# ARP_Odyssey_Ring_Mod_1_1.net
KiCad netlist of a schematic drawn in EAGLE
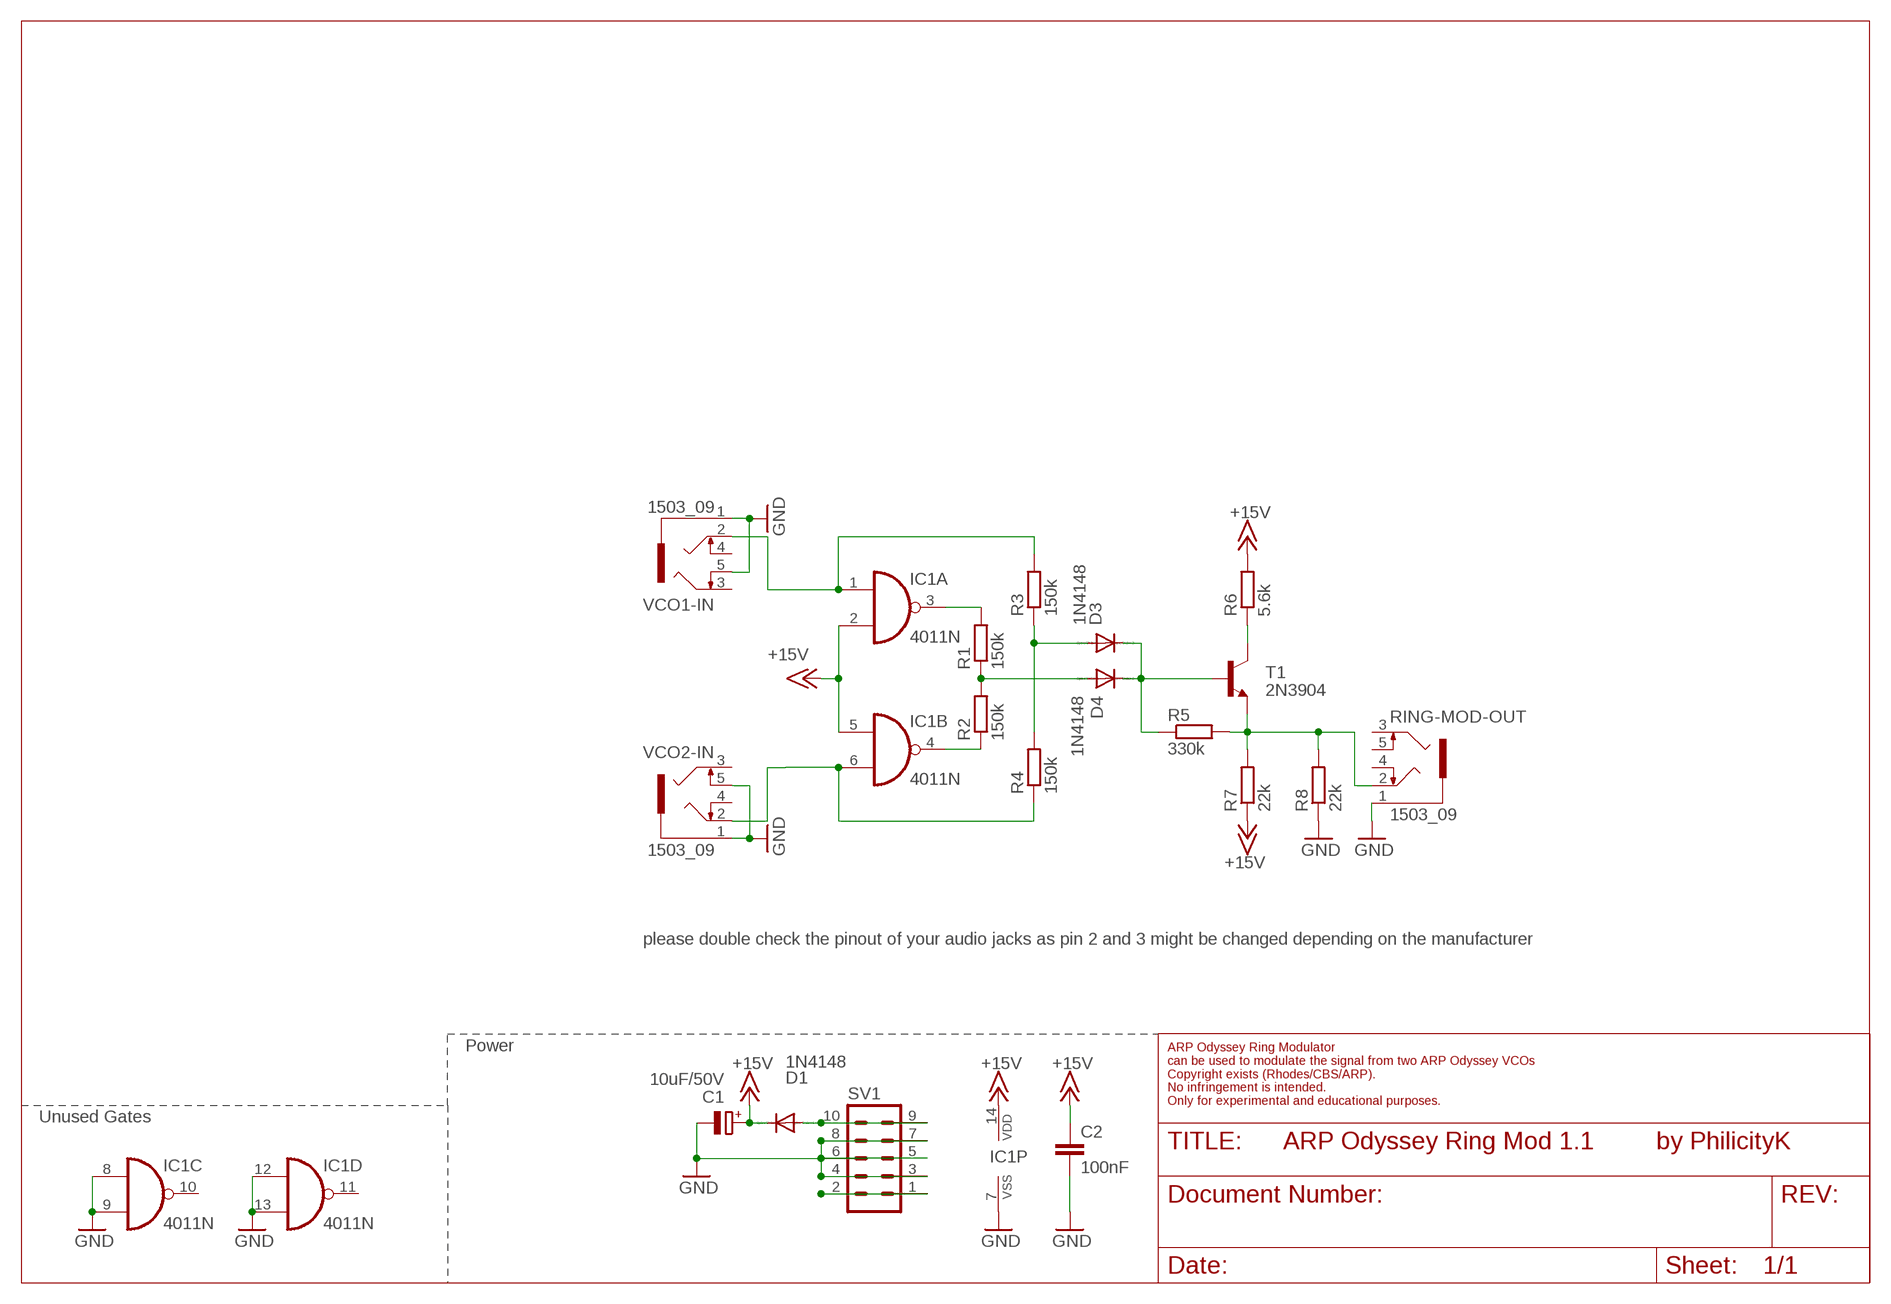
[diagram p0: schematic, sheet 1]

(export (version "E")
  (design (tool "Eeschema 10.0.6"))
  (components
    (comp (ref "C1")
      (value "10uF/50V")
      (footprint "eagle-import:E3,5-8")
      (libsource (lib "eagle-import") (part "CPOL-EUE3.5-8"))
    )
    (comp (ref "C2")
      (value "100nF")
      (footprint "eagle-import:C050-024X044")
      (libsource (lib "eagle-import") (part "C-EU050-024X044"))
    )
    (comp (ref "D1")
      (value "1N4148")
      (footprint "eagle-import:DO35-7")
      (libsource (lib "eagle-import") (part "1N4148DO35-7"))
    )
    (comp (ref "D3")
      (value "1N4148")
      (footprint "eagle-import:DO35-7")
      (libsource (lib "eagle-import") (part "1N4148DO35-7"))
    )
    (comp (ref "D4")
      (value "1N4148")
      (footprint "eagle-import:DO35-7")
      (libsource (lib "eagle-import") (part "1N4148DO35-7"))
    )
    (comp (ref "IC1")
      (value "4011N")
      (footprint "eagle-import:DIL14")
      (libsource (lib "eagle-import") (part "4011N"))
    )
    (comp (ref "R1")
      (value "150k")
      (footprint "eagle-import:0207_7")
      (libsource (lib "eagle-import") (part "R-EU_0207/7"))
    )
    (comp (ref "R2")
      (value "150k")
      (footprint "eagle-import:0207_7")
      (libsource (lib "eagle-import") (part "R-EU_0207/7"))
    )
    (comp (ref "R3")
      (value "150k")
      (footprint "eagle-import:0207_7")
      (libsource (lib "eagle-import") (part "R-EU_0207/7"))
    )
    (comp (ref "R4")
      (value "150k")
      (footprint "eagle-import:0207_7")
      (libsource (lib "eagle-import") (part "R-EU_0207/7"))
    )
    (comp (ref "R5")
      (value "330k")
      (footprint "eagle-import:0207_7")
      (libsource (lib "eagle-import") (part "R-EU_0207/7"))
    )
    (comp (ref "R6")
      (value "5.6k")
      (footprint "eagle-import:0207_7")
      (libsource (lib "eagle-import") (part "R-EU_0207/7"))
    )
    (comp (ref "R7")
      (value "22k")
      (footprint "eagle-import:0207_7")
      (libsource (lib "eagle-import") (part "R-EU_0207/7"))
    )
    (comp (ref "R8")
      (value "22k")
      (footprint "eagle-import:0207_7")
      (libsource (lib "eagle-import") (part "R-EU_0207/7"))
    )
    (comp (ref "RING-MOD-OUT")
      (value "1503_09")
      (footprint "eagle-import:1503_09")
      (libsource (lib "eagle-import") (part "1503_09"))
    )
    (comp (ref "SV1")
      (value "ML10")
      (footprint "eagle-import:ML10")
      (libsource (lib "eagle-import") (part "ML10"))
    )
    (comp (ref "T1")
      (value "2N3904")
      (footprint "eagle-import:TO92-EBC")
      (libsource (lib "eagle-import") (part "-NPN-TO92-EBC2N3904"))
    )
    (comp (ref "VCO1-IN")
      (value "1503_09")
      (footprint "eagle-import:1503_09")
      (libsource (lib "eagle-import") (part "1503_09"))
    )
    (comp (ref "VCO2-IN")
      (value "1503_09")
      (footprint "eagle-import:1503_09")
      (libsource (lib "eagle-import") (part "1503_09"))
    )
  )
  (nets
    (net (code "1") (name "+15V") (class "Default")
      (node (ref "C1") (pin "+") (pinfunction "+_+") (pintype "passive"))
      (node (ref "C2") (pin "1") (pinfunction "1_1") (pintype "passive"))
      (node (ref "D1") (pin "C") (pinfunction "C_C") (pintype "passive"))
      (node (ref "IC1") (pin "14") (pinfunction "VDD_14") (pintype "power_in"))
      (node (ref "IC1") (pin "2") (pinfunction "I1_2") (pintype "input"))
      (node (ref "IC1") (pin "5") (pinfunction "I0_5") (pintype "input"))
      (node (ref "R6") (pin "2") (pinfunction "2_2") (pintype "passive"))
      (node (ref "R7") (pin "1") (pinfunction "1_1") (pintype "passive"))
    )
    (net (code "2") (name "GND") (class "Default")
      (node (ref "C1") (pin "-") (pinfunction "-_-") (pintype "passive"))
      (node (ref "C2") (pin "2") (pinfunction "2_2") (pintype "passive"))
      (node (ref "IC1") (pin "12") (pinfunction "I0_12") (pintype "input"))
      (node (ref "IC1") (pin "13") (pinfunction "I1_13") (pintype "input"))
      (node (ref "IC1") (pin "7") (pinfunction "VSS_7") (pintype "power_in"))
      (node (ref "IC1") (pin "8") (pinfunction "I0_8") (pintype "input"))
      (node (ref "IC1") (pin "9") (pinfunction "I1_9") (pintype "input"))
      (node (ref "R8") (pin "1") (pinfunction "1_1") (pintype "passive"))
      (node (ref "RING-MOD-OUT") (pin "1") (pinfunction "1_1") (pintype "passive"))
      (node (ref "SV1") (pin "3") (pinfunction "3_3") (pintype "passive"))
      (node (ref "SV1") (pin "4") (pinfunction "4_4") (pintype "passive"))
      (node (ref "SV1") (pin "5") (pinfunction "5_5") (pintype "passive"))
      (node (ref "SV1") (pin "6") (pinfunction "6_6") (pintype "passive"))
      (node (ref "SV1") (pin "7") (pinfunction "7_7") (pintype "passive"))
      (node (ref "SV1") (pin "8") (pinfunction "8_8") (pintype "passive"))
      (node (ref "VCO1-IN") (pin "1") (pinfunction "1_1") (pintype "passive"))
      (node (ref "VCO1-IN") (pin "5") (pinfunction "5_5") (pintype "passive"))
      (node (ref "VCO2-IN") (pin "1") (pinfunction "1_1") (pintype "passive"))
      (node (ref "VCO2-IN") (pin "5") (pinfunction "5_5") (pintype "passive"))
    )
    (net (code "3") (name "Net-(D1-PadA)") (class "Default")
      (node (ref "D1") (pin "A") (pinfunction "A_A") (pintype "passive"))
      (node (ref "SV1") (pin "10") (pinfunction "10_10") (pintype "passive"))
      (node (ref "SV1") (pin "9") (pinfunction "9_9") (pintype "passive"))
    )
    (net (code "4") (name "Net-(D3-PadA)") (class "Default")
      (node (ref "D3") (pin "A") (pinfunction "A_A") (pintype "passive"))
      (node (ref "R3") (pin "1") (pinfunction "1_1") (pintype "passive"))
      (node (ref "R4") (pin "2") (pinfunction "2_2") (pintype "passive"))
    )
    (net (code "5") (name "Net-(D3-PadC)") (class "Default")
      (node (ref "D3") (pin "C") (pinfunction "C_C") (pintype "passive"))
      (node (ref "D4") (pin "C") (pinfunction "C_C") (pintype "passive"))
      (node (ref "R5") (pin "1") (pinfunction "1_1") (pintype "passive"))
      (node (ref "T1") (pin "B") (pinfunction "B_B") (pintype "passive"))
    )
    (net (code "6") (name "Net-(D4-PadA)") (class "Default")
      (node (ref "D4") (pin "A") (pinfunction "A_A") (pintype "passive"))
      (node (ref "R1") (pin "1") (pinfunction "1_1") (pintype "passive"))
      (node (ref "R2") (pin "2") (pinfunction "2_2") (pintype "passive"))
    )
    (net (code "7") (name "Net-(IC1A-I0)") (class "Default")
      (node (ref "IC1") (pin "1") (pinfunction "I0_1") (pintype "input"))
      (node (ref "R3") (pin "2") (pinfunction "2_2") (pintype "passive"))
      (node (ref "VCO1-IN") (pin "2") (pinfunction "2_2") (pintype "passive"))
    )
    (net (code "8") (name "Net-(IC1A-O)") (class "Default")
      (node (ref "IC1") (pin "3") (pinfunction "O_3") (pintype "output"))
      (node (ref "R1") (pin "2") (pinfunction "2_2") (pintype "passive"))
    )
    (net (code "9") (name "Net-(IC1B-I1)") (class "Default")
      (node (ref "IC1") (pin "6") (pinfunction "I1_6") (pintype "input"))
      (node (ref "R4") (pin "1") (pinfunction "1_1") (pintype "passive"))
      (node (ref "VCO2-IN") (pin "2") (pinfunction "2_2") (pintype "passive"))
    )
    (net (code "10") (name "Net-(IC1B-O)") (class "Default")
      (node (ref "IC1") (pin "4") (pinfunction "O_4") (pintype "output"))
      (node (ref "R2") (pin "1") (pinfunction "1_1") (pintype "passive"))
    )
    (net (code "11") (name "Net-(R5-Pad2)") (class "Default")
      (node (ref "R5") (pin "2") (pinfunction "2_2") (pintype "passive"))
      (node (ref "R7") (pin "2") (pinfunction "2_2") (pintype "passive"))
      (node (ref "R8") (pin "2") (pinfunction "2_2") (pintype "passive"))
      (node (ref "RING-MOD-OUT") (pin "2") (pinfunction "2_2") (pintype "passive"))
      (node (ref "T1") (pin "E") (pinfunction "E_E") (pintype "passive"))
    )
    (net (code "12") (name "Net-(R6-Pad1)") (class "Default")
      (node (ref "R6") (pin "1") (pinfunction "1_1") (pintype "passive"))
      (node (ref "T1") (pin "C") (pinfunction "C_C") (pintype "passive"))
    )
    (net (code "13") (name "Net-(SV1-Pad1)") (class "Default")
      (node (ref "SV1") (pin "1") (pinfunction "1_1") (pintype "passive"))
      (node (ref "SV1") (pin "2") (pinfunction "2_2") (pintype "passive"))
    )
    (net (code "14") (name "unconnected-(IC1C-O-Pad10)") (class "Default")
      (node (ref "IC1") (pin "10") (pinfunction "O_10") (pintype "output"))
    )
    (net (code "15") (name "unconnected-(IC1D-O-Pad11)") (class "Default")
      (node (ref "IC1") (pin "11") (pinfunction "O_11") (pintype "output"))
    )
    (net (code "16") (name "unconnected-(RING-MOD-OUT-Pad3)") (class "Default")
      (node (ref "RING-MOD-OUT") (pin "3") (pinfunction "3_3") (pintype "passive"))
    )
    (net (code "17") (name "unconnected-(RING-MOD-OUT-Pad4)") (class "Default")
      (node (ref "RING-MOD-OUT") (pin "4") (pinfunction "4_4") (pintype "passive"))
    )
    (net (code "18") (name "unconnected-(RING-MOD-OUT-Pad5)") (class "Default")
      (node (ref "RING-MOD-OUT") (pin "5") (pinfunction "5_5") (pintype "passive"))
    )
    (net (code "19") (name "unconnected-(VCO1-IN-Pad3)") (class "Default")
      (node (ref "VCO1-IN") (pin "3") (pinfunction "3_3") (pintype "passive"))
    )
    (net (code "20") (name "unconnected-(VCO1-IN-Pad4)") (class "Default")
      (node (ref "VCO1-IN") (pin "4") (pinfunction "4_4") (pintype "passive"))
    )
    (net (code "21") (name "unconnected-(VCO2-IN-Pad3)") (class "Default")
      (node (ref "VCO2-IN") (pin "3") (pinfunction "3_3") (pintype "passive"))
    )
    (net (code "22") (name "unconnected-(VCO2-IN-Pad4)") (class "Default")
      (node (ref "VCO2-IN") (pin "4") (pinfunction "4_4") (pintype "passive"))
    )
  )
)
